# ECUEXT1_23.net
KiCad netlist of a schematic drawn in Altium Designer
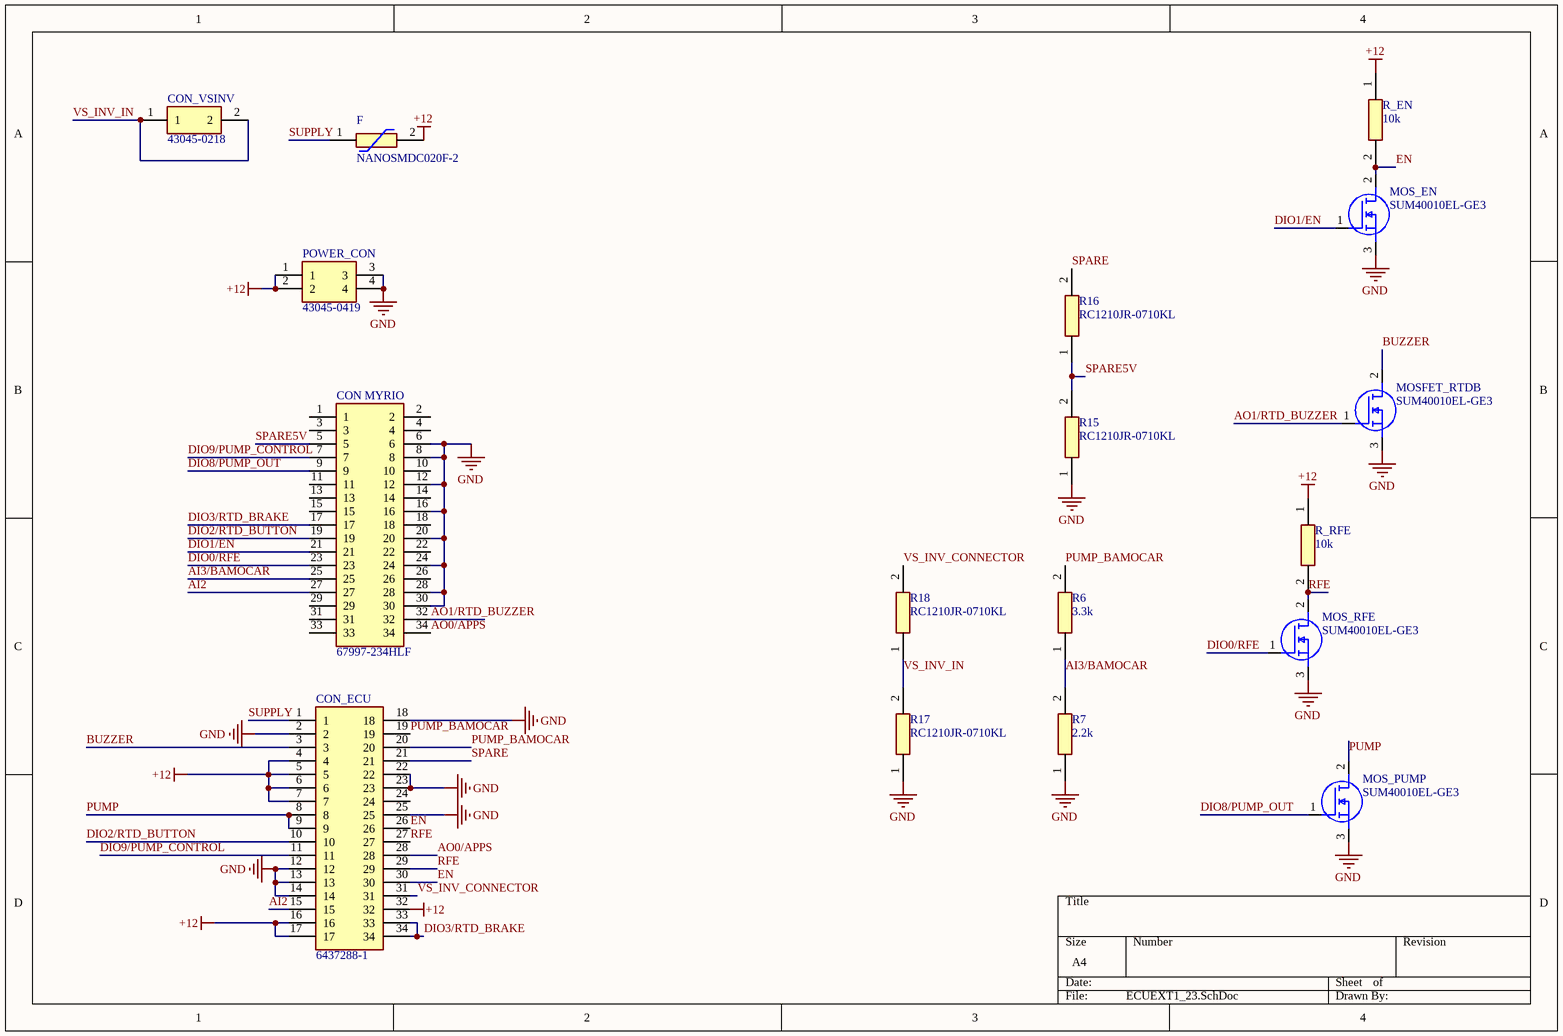
[diagram p0: ECUEXT1_23.SchDoc]

(export (version "E")
  (design (tool "Eeschema 10.0.6"))
  (components
    (comp (ref "CON MYRIO")
      (value "67997-234HLF")
      (footprint "SamacSys:HDRV34W67P254_2X17_4318X483X858P")
      (description "Connector")
      (fields (field (name "MOUSER PART NUMBER") "649-67997-234HLF"))
      (libsource (lib "*") (part "67997-234HLF"))
    )
    (comp (ref "CON_ECU")
      (value "6437288-1")
      (footprint "SamacSys:6437288-1")
      (description "Connector")
      (fields (field (name "MOUSER PART NUMBER") "571-6437288-1"))
      (libsource (lib "SamacSys") (part "6437288-1"))
    )
    (comp (ref "CON_VSINV")
      (value "43045-0218")
      (footprint "SamacSys:43045-02YY_181920")
      (description "Connector")
      (fields (field (name "MOUSER PART NUMBER") "538-43045-0218"))
      (libsource (lib "SamacSys") (part "43045-0218"))
    )
    (comp (ref "F")
      (value "NANOSMDC020F-2")
      (footprint "SamacSys:NANOSMDC016F2")
      (description "Resettable Fuse")
      (fields (field (name "MOUSER PART NUMBER") "650-NANOSMDC020F-2"))
      (libsource (lib "*") (part "NANOSMDC020F-2"))
    )
    (comp (ref "MOSFET_RTDB")
      (value "SUM40010EL-GE3")
      (footprint "SamacSys:SUM40010ELGE3")
      (description "MOSFET (N-Channel)")
      (fields (field (name "MOUSER PART NUMBER") "78-SUM40010EL-GE3"))
      (libsource (lib "SamacSys") (part "SUM40010EL-GE3"))
    )
    (comp (ref "MOS_EN")
      (value "SUM40010EL-GE3")
      (footprint "SamacSys:SUM40010ELGE3")
      (description "MOSFET (N-Channel)")
      (fields (field (name "MOUSER PART NUMBER") "78-SUM40010EL-GE3"))
      (libsource (lib "SamacSys") (part "SUM40010EL-GE3"))
    )
    (comp (ref "MOS_PUMP")
      (value "SUM40010EL-GE3")
      (footprint "SamacSys:SUM40010ELGE3")
      (description "MOSFET (N-Channel)")
      (fields (field (name "MOUSER PART NUMBER") "78-SUM40010EL-GE3"))
      (libsource (lib "SamacSys") (part "SUM40010EL-GE3"))
    )
    (comp (ref "MOS_RFE")
      (value "SUM40010EL-GE3")
      (footprint "SamacSys:SUM40010ELGE3")
      (description "MOSFET (N-Channel)")
      (fields (field (name "MOUSER PART NUMBER") "78-SUM40010EL-GE3"))
      (libsource (lib "SamacSys") (part "SUM40010EL-GE3"))
    )
    (comp (ref "POWER_CON")
      (value "43045-0419")
      (footprint "SamacSys:43045-04YY_181920")
      (description "Connector")
      (fields (field (name "MOUSER PART NUMBER") "538-43045-0419"))
      (libsource (lib "SamacSys") (part "43045-0419"))
    )
    (comp (ref "R6")
      (value "3.3k")
      (footprint "SamacSys:RESC3126X60N")
      (description "Resistor")
      (fields
        (field (name "MANUFACTURER_PART_NUMBER") "RC1210JR-0710KL")
        (field (name "MOUSER PART NUMBER") "603-RC1210JR-0710KL")
      )
      (libsource (lib "") (part "RC1210JR-0710KL_1"))
    )
    (comp (ref "R7")
      (value "2.2k")
      (footprint "SamacSys:RESC3126X60N")
      (description "Resistor")
      (fields
        (field (name "MANUFACTURER_PART_NUMBER") "RC1210JR-0710KL")
        (field (name "MOUSER PART NUMBER") "603-RC1210JR-0710KL")
      )
      (libsource (lib "") (part "RC1210JR-0710KL_1"))
    )
    (comp (ref "R15")
      (value "RC1210JR-0710KL")
      (footprint "SamacSys:RESC3126X60N")
      (description "Resistor")
      (fields (field (name "MOUSER PART NUMBER") "603-RC1210JR-0710KL"))
      (libsource (lib "SamacSys") (part "RC1210JR-0710KL"))
    )
    (comp (ref "R16")
      (value "RC1210JR-0710KL")
      (footprint "SamacSys:RESC3126X60N")
      (description "Resistor")
      (fields (field (name "MOUSER PART NUMBER") "603-RC1210JR-0710KL"))
      (libsource (lib "SamacSys") (part "RC1210JR-0710KL"))
    )
    (comp (ref "R17")
      (value "RC1210JR-0710KL")
      (footprint "SamacSys:RESC3126X60N")
      (description "Resistor")
      (fields (field (name "MOUSER PART NUMBER") "603-RC1210JR-0710KL"))
      (libsource (lib "SamacSys") (part "RC1210JR-0710KL"))
    )
    (comp (ref "R18")
      (value "RC1210JR-0710KL")
      (footprint "SamacSys:RESC3126X60N")
      (description "Resistor")
      (fields (field (name "MOUSER PART NUMBER") "603-RC1210JR-0710KL"))
      (libsource (lib "SamacSys") (part "RC1210JR-0710KL"))
    )
    (comp (ref "R_EN")
      (value "10k")
      (footprint "SamacSys:RESC3126X60N")
      (description "Resistor")
      (fields
        (field (name "MANUFACTURER_PART_NUMBER") "RC1210JR-0710KL")
        (field (name "MOUSER PART NUMBER") "603-RC1210JR-0710KL")
      )
      (libsource (lib "*") (part "RC1210JR-0710KL"))
    )
    (comp (ref "R_RFE")
      (value "10k")
      (footprint "SamacSys:RESC3126X60N")
      (description "Resistor")
      (fields
        (field (name "MANUFACTURER_PART_NUMBER") "RC1210JR-0710KL")
        (field (name "MOUSER PART NUMBER") "603-RC1210JR-0710KL")
      )
      (libsource (lib "*") (part "RC1210JR-0710KL"))
    )
  )
  (nets
    (net (code "1") (name "+12") (class "Default")
      (node (ref "CON_ECU") (pin "16") (pinfunction "16_16") (pintype "passive"))
      (node (ref "CON_ECU") (pin "17") (pinfunction "17_17") (pintype "passive"))
      (node (ref "CON_ECU") (pin "32") (pinfunction "32_32") (pintype "passive"))
      (node (ref "CON_ECU") (pin "4") (pinfunction "4_4") (pintype "passive"))
      (node (ref "CON_ECU") (pin "5") (pinfunction "5_5") (pintype "passive"))
      (node (ref "CON_ECU") (pin "6") (pinfunction "6_6") (pintype "passive"))
      (node (ref "CON_ECU") (pin "7") (pinfunction "7_7") (pintype "passive"))
      (node (ref "F") (pin "2") (pinfunction "2_2") (pintype "passive"))
      (node (ref "POWER_CON") (pin "1") (pinfunction "1_1") (pintype "passive"))
      (node (ref "POWER_CON") (pin "2") (pinfunction "2_2") (pintype "passive"))
      (node (ref "R_EN") (pin "1") (pinfunction "1_1") (pintype "passive"))
      (node (ref "R_RFE") (pin "1") (pinfunction "1_1") (pintype "passive"))
    )
    (net (code "2") (name "/AI2") (class "Default")
      (node (ref "CON MYRIO") (pin "27") (pinfunction "27_27") (pintype "passive"))
      (node (ref "CON_ECU") (pin "15") (pinfunction "15_15") (pintype "passive"))
    )
    (net (code "3") (name "/AI3{slash}BAMOCAR") (class "Default")
      (node (ref "CON MYRIO") (pin "25") (pinfunction "25_25") (pintype "passive"))
      (node (ref "R6") (pin "1") (pinfunction "1_1") (pintype "passive"))
      (node (ref "R7") (pin "2") (pinfunction "2_2") (pintype "passive"))
    )
    (net (code "4") (name "/AO0{slash}APPS") (class "Default")
      (node (ref "CON MYRIO") (pin "34") (pinfunction "34_34") (pintype "passive"))
      (node (ref "CON_ECU") (pin "28") (pinfunction "28_28") (pintype "passive"))
    )
    (net (code "5") (name "/AO1{slash}RTD_BUZZER") (class "Default")
      (node (ref "CON MYRIO") (pin "32") (pinfunction "32_32") (pintype "passive"))
      (node (ref "MOSFET_RTDB") (pin "1") (pinfunction "G_1") (pintype "passive"))
    )
    (net (code "6") (name "/BUZZER") (class "Default")
      (node (ref "CON_ECU") (pin "3") (pinfunction "3_3") (pintype "passive"))
      (node (ref "MOSFET_RTDB") (pin "2") (pinfunction "D_2") (pintype "passive"))
    )
    (net (code "7") (name "/DIO0{slash}RFE") (class "Default")
      (node (ref "CON MYRIO") (pin "23") (pinfunction "23_23") (pintype "passive"))
      (node (ref "MOS_RFE") (pin "1") (pinfunction "G_1") (pintype "passive"))
    )
    (net (code "8") (name "/DIO1{slash}EN") (class "Default")
      (node (ref "CON MYRIO") (pin "21") (pinfunction "21_21") (pintype "passive"))
      (node (ref "MOS_EN") (pin "1") (pinfunction "G_1") (pintype "passive"))
    )
    (net (code "9") (name "/DIO2{slash}RTD_BUTTON") (class "Default")
      (node (ref "CON MYRIO") (pin "19") (pinfunction "19_19") (pintype "passive"))
      (node (ref "CON_ECU") (pin "10") (pinfunction "10_10") (pintype "passive"))
    )
    (net (code "10") (name "/DIO3{slash}RTD_BRAKE") (class "Default")
      (node (ref "CON MYRIO") (pin "17") (pinfunction "17_17") (pintype "passive"))
      (node (ref "CON_ECU") (pin "33") (pinfunction "33_33") (pintype "passive"))
      (node (ref "CON_ECU") (pin "34") (pinfunction "34_34") (pintype "passive"))
    )
    (net (code "11") (name "/DIO8{slash}PUMP_OUT") (class "Default")
      (node (ref "CON MYRIO") (pin "9") (pinfunction "9_9") (pintype "passive"))
      (node (ref "MOS_PUMP") (pin "1") (pinfunction "G_1") (pintype "passive"))
    )
    (net (code "12") (name "/DIO9{slash}PUMP_CONTROL") (class "Default")
      (node (ref "CON MYRIO") (pin "7") (pinfunction "7_7") (pintype "passive"))
      (node (ref "CON_ECU") (pin "11") (pinfunction "11_11") (pintype "passive"))
    )
    (net (code "13") (name "/EN") (class "Default")
      (node (ref "CON_ECU") (pin "26") (pinfunction "26_26") (pintype "passive"))
      (node (ref "CON_ECU") (pin "30") (pinfunction "30_30") (pintype "passive"))
      (node (ref "MOS_EN") (pin "2") (pinfunction "D_2") (pintype "passive"))
      (node (ref "R_EN") (pin "2") (pinfunction "2_2") (pintype "passive"))
    )
    (net (code "14") (name "/PUMP") (class "Default")
      (node (ref "CON_ECU") (pin "8") (pinfunction "8_8") (pintype "passive"))
      (node (ref "CON_ECU") (pin "9") (pinfunction "9_9") (pintype "passive"))
      (node (ref "MOS_PUMP") (pin "2") (pinfunction "D_2") (pintype "passive"))
    )
    (net (code "15") (name "/PUMP_BAMOCAR") (class "Default")
      (node (ref "CON_ECU") (pin "19") (pinfunction "19_19") (pintype "passive"))
      (node (ref "CON_ECU") (pin "20") (pinfunction "20_20") (pintype "passive"))
      (node (ref "R6") (pin "2") (pinfunction "2_2") (pintype "passive"))
    )
    (net (code "16") (name "/RFE") (class "Default")
      (node (ref "CON_ECU") (pin "27") (pinfunction "27_27") (pintype "passive"))
      (node (ref "CON_ECU") (pin "29") (pinfunction "29_29") (pintype "passive"))
      (node (ref "MOS_RFE") (pin "2") (pinfunction "D_2") (pintype "passive"))
      (node (ref "R_RFE") (pin "2") (pinfunction "2_2") (pintype "passive"))
    )
    (net (code "17") (name "/SPARE") (class "Default")
      (node (ref "CON_ECU") (pin "21") (pinfunction "21_21") (pintype "passive"))
      (node (ref "R16") (pin "2") (pinfunction "2_2") (pintype "passive"))
    )
    (net (code "18") (name "/SPARE5V") (class "Default")
      (node (ref "CON MYRIO") (pin "5") (pinfunction "5_5") (pintype "passive"))
      (node (ref "R15") (pin "2") (pinfunction "2_2") (pintype "passive"))
      (node (ref "R16") (pin "1") (pinfunction "1_1") (pintype "passive"))
    )
    (net (code "19") (name "/SUPPLY") (class "Default")
      (node (ref "CON_ECU") (pin "1") (pinfunction "1_1") (pintype "passive"))
      (node (ref "F") (pin "1") (pinfunction "1_1") (pintype "passive"))
    )
    (net (code "20") (name "/VS_INV_CONNECTOR") (class "Default")
      (node (ref "CON_ECU") (pin "31") (pinfunction "31_31") (pintype "passive"))
      (node (ref "R18") (pin "2") (pinfunction "2_2") (pintype "passive"))
    )
    (net (code "21") (name "/VS_INV_IN") (class "Default")
      (node (ref "CON_VSINV") (pin "1") (pinfunction "1_1") (pintype "passive"))
      (node (ref "CON_VSINV") (pin "2") (pinfunction "2_2") (pintype "passive"))
      (node (ref "R17") (pin "2") (pinfunction "2_2") (pintype "passive"))
      (node (ref "R18") (pin "1") (pinfunction "1_1") (pintype "passive"))
    )
    (net (code "22") (name "GND") (class "Default")
      (node (ref "CON MYRIO") (pin "12") (pinfunction "12_12") (pintype "passive"))
      (node (ref "CON MYRIO") (pin "16") (pinfunction "16_16") (pintype "passive"))
      (node (ref "CON MYRIO") (pin "20") (pinfunction "20_20") (pintype "passive"))
      (node (ref "CON MYRIO") (pin "24") (pinfunction "24_24") (pintype "passive"))
      (node (ref "CON MYRIO") (pin "28") (pinfunction "28_28") (pintype "passive"))
      (node (ref "CON MYRIO") (pin "30") (pinfunction "30_30") (pintype "passive"))
      (node (ref "CON MYRIO") (pin "6") (pinfunction "6_6") (pintype "passive"))
      (node (ref "CON MYRIO") (pin "8") (pinfunction "8_8") (pintype "passive"))
      (node (ref "CON_ECU") (pin "12") (pinfunction "12_12") (pintype "passive"))
      (node (ref "CON_ECU") (pin "13") (pinfunction "13_13") (pintype "passive"))
      (node (ref "CON_ECU") (pin "14") (pinfunction "14_14") (pintype "passive"))
      (node (ref "CON_ECU") (pin "18") (pinfunction "18_18") (pintype "passive"))
      (node (ref "CON_ECU") (pin "2") (pinfunction "2_2") (pintype "passive"))
      (node (ref "CON_ECU") (pin "22") (pinfunction "22_22") (pintype "passive"))
      (node (ref "CON_ECU") (pin "23") (pinfunction "23_23") (pintype "passive"))
      (node (ref "CON_ECU") (pin "25") (pinfunction "25_25") (pintype "passive"))
      (node (ref "MOSFET_RTDB") (pin "3") (pinfunction "S_3") (pintype "passive"))
      (node (ref "MOS_EN") (pin "3") (pinfunction "S_3") (pintype "passive"))
      (node (ref "MOS_PUMP") (pin "3") (pinfunction "S_3") (pintype "passive"))
      (node (ref "MOS_RFE") (pin "3") (pinfunction "S_3") (pintype "passive"))
      (node (ref "POWER_CON") (pin "3") (pinfunction "3_3") (pintype "passive"))
      (node (ref "POWER_CON") (pin "4") (pinfunction "4_4") (pintype "passive"))
      (node (ref "R15") (pin "1") (pinfunction "1_1") (pintype "passive"))
      (node (ref "R17") (pin "1") (pinfunction "1_1") (pintype "passive"))
      (node (ref "R7") (pin "1") (pinfunction "1_1") (pintype "passive"))
    )
    (net (code "23") (name "unconnected-(CON MYRIO-Pad1)") (class "Default")
      (node (ref "CON MYRIO") (pin "1") (pinfunction "1_1") (pintype "passive"))
    )
    (net (code "24") (name "unconnected-(CON MYRIO-Pad2)") (class "Default")
      (node (ref "CON MYRIO") (pin "2") (pinfunction "2_2") (pintype "passive"))
    )
    (net (code "25") (name "unconnected-(CON MYRIO-Pad3)") (class "Default")
      (node (ref "CON MYRIO") (pin "3") (pinfunction "3_3") (pintype "passive"))
    )
    (net (code "26") (name "unconnected-(CON MYRIO-Pad4)") (class "Default")
      (node (ref "CON MYRIO") (pin "4") (pinfunction "4_4") (pintype "passive"))
    )
    (net (code "27") (name "unconnected-(CON MYRIO-Pad10)") (class "Default")
      (node (ref "CON MYRIO") (pin "10") (pinfunction "10_10") (pintype "passive"))
    )
    (net (code "28") (name "unconnected-(CON MYRIO-Pad11)") (class "Default")
      (node (ref "CON MYRIO") (pin "11") (pinfunction "11_11") (pintype "passive"))
    )
    (net (code "29") (name "unconnected-(CON MYRIO-Pad13)") (class "Default")
      (node (ref "CON MYRIO") (pin "13") (pinfunction "13_13") (pintype "passive"))
    )
    (net (code "30") (name "unconnected-(CON MYRIO-Pad14)") (class "Default")
      (node (ref "CON MYRIO") (pin "14") (pinfunction "14_14") (pintype "passive"))
    )
    (net (code "31") (name "unconnected-(CON MYRIO-Pad15)") (class "Default")
      (node (ref "CON MYRIO") (pin "15") (pinfunction "15_15") (pintype "passive"))
    )
    (net (code "32") (name "unconnected-(CON MYRIO-Pad18)") (class "Default")
      (node (ref "CON MYRIO") (pin "18") (pinfunction "18_18") (pintype "passive"))
    )
    (net (code "33") (name "unconnected-(CON MYRIO-Pad22)") (class "Default")
      (node (ref "CON MYRIO") (pin "22") (pinfunction "22_22") (pintype "passive"))
    )
    (net (code "34") (name "unconnected-(CON MYRIO-Pad26)") (class "Default")
      (node (ref "CON MYRIO") (pin "26") (pinfunction "26_26") (pintype "passive"))
    )
    (net (code "35") (name "unconnected-(CON MYRIO-Pad29)") (class "Default")
      (node (ref "CON MYRIO") (pin "29") (pinfunction "29_29") (pintype "passive"))
    )
    (net (code "36") (name "unconnected-(CON MYRIO-Pad31)") (class "Default")
      (node (ref "CON MYRIO") (pin "31") (pinfunction "31_31") (pintype "passive"))
    )
    (net (code "37") (name "unconnected-(CON MYRIO-Pad33)") (class "Default")
      (node (ref "CON MYRIO") (pin "33") (pinfunction "33_33") (pintype "passive"))
    )
    (net (code "38") (name "unconnected-(CON_ECU-Pad24)") (class "Default")
      (node (ref "CON_ECU") (pin "24") (pinfunction "24_24") (pintype "passive"))
    )
  )
)
